# Boost-Shield-V1_5.net
KiCad netlist of a schematic drawn in Altium Designer
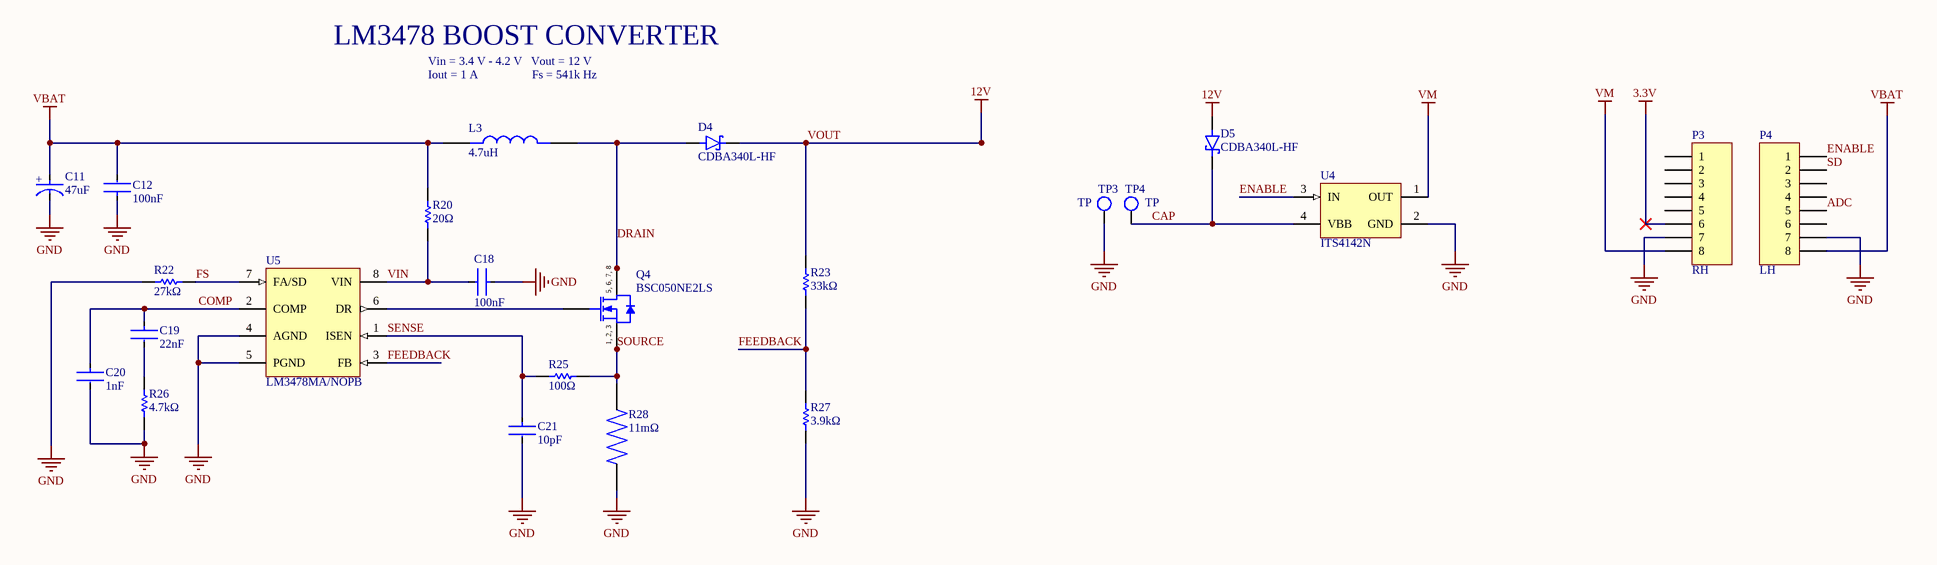
[diagram p0: Boost-Shield-V1.5.SchDoc]

(export (version "E")
  (design (tool "Eeschema 10.0.6"))
  (components
    (comp (ref "C11")
      (value "47uF")
      (footprint "FP-F38M-MFG")
      (description "CAP TANT POLY 47UF 6.3V SMD \r\nF380J476MMAAXEH3")
      (fields
        (field (name "OCTOPART") "https://octopart.com/f380j476mmaaxeh3-avx-67040374")
        (field (name "MANUFACTURER") "AVX")
      )
      (libsource (lib "Altium Content Vault") (part "cf48714ba7e38822c1575c7ec0b6d1f"))
    )
    (comp (ref "C12")
      (value "100nF")
      (footprint "FP-CL10-IPC_C")
      (description "Cap Ceramic 100nF 50V X7R ±20% Pad SMD 0603 +125°C T/R\r\nCL10B104MB8NNNC")
      (fields (field (name "TOLERANCE") "20%"))
      (libsource (lib "Altium Content Vault") (part "b4654b650e69147ec39a6b967a45e02"))
    )
    (comp (ref "C18")
      (value "100nF")
      (footprint "FP-CL10-IPC_C")
      (description "Cap Ceramic 100nF 50V X7R ±20% Pad SMD 0603 +125°C T/R\r\nCL10B104MB8NNNC")
      (fields (field (name "TOLERANCE") "20%"))
      (libsource (lib "Altium Content Vault") (part "b4654b650e69147ec39a6b967a45e02"))
    )
    (comp (ref "C19")
      (value "22nF")
      (footprint "FP-CC0603-DA-MFG")
      (description "0603 22 nF 50 V ±10 % Tolerance X7R SMT Multilayer Ceramic Capacitor\r\nCC0603KRX7R9BB223")
      (fields
        (field (name "MANUFACTURER") "YAGEO")
        (field (name "MANUFACTURER PART NUMBER") "CC0603KRX7R9BB223")
      )
      (libsource (lib "Altium Content Vault") (part "11868f565c42a9108669ba33697ecf6"))
    )
    (comp (ref "C20")
      (value "1nF")
      (footprint "FP-0603-L_1_6_0_15-W_0_81-IPC_C")
      (description "CAP CER 10000PF 50V X7R 0603\r\n06035C103KAT4A")
      (fields (field (name "TOLERANCE") "10%") (field (name "VOLTAGE") "50V"))
      (libsource (lib "Altium Content Vault") (part "02cd4be3c70576c341d710602a673aa"))
    )
    (comp (ref "C21")
      (value "10pF")
      (footprint "FP-C0603C-CF-MFG")
      (description "CAP CER 10PF 100V 5% NP0 0603\r\nC0603C100J1GACTU")
      (fields
        (field (name "MANUFACTURER PART NUMBER") "C0603C100J1GACTU")
        (field (name "MANUFACTURER") "KEMET")
      )
      (libsource (lib "Altium Content Vault") (part "b4654b650e69147ec39a6b967a45e02"))
    )
    (comp (ref "D4")
      (value "CDBA340L-HF")
      (footprint "DIOM5225X250N")
      (description "DIODE SCHOTTKY 40V 3A DO214AC")
      (fields (field (name "MANUFACTURER") "Comchip"))
      (libsource (lib "Boost-Shield") (part "CDBA340L-HF"))
    )
    (comp (ref "D5")
      (value "CDBA340L-HF")
      (footprint "DIOM5225X250N")
      (description "DIODE SCHOTTKY 40V 3A DO214AC")
      (fields (field (name "MANUFACTURER") "Comchip"))
      (libsource (lib "Boost-Shield") (part "CDBA340L-HF"))
    )
    (comp (ref "L3")
      (value "4.7uH")
      (footprint "IND_ETQP4M4R7KFN")
      (description "Fixed Ind 4.7UH 7.3A 22.77MOHM")
      (fields
        (field (name "MANUFACTURER") "Panasonic")
        (field (name "MANUFACTURER PART NUMBER") "ETQ-P4M4R7KFN")
      )
      (libsource (lib "Boost-Shield") (part "ETQ-P4M4R7KFN"))
    )
    (comp (ref "P3")
      (value "RH")
      (footprint "HDR1X8")
      (description "Header, 8-Pin")
      (fields (field (name "PUBLISHER") "Altium Limited"))
      (libsource (lib "") (part "Header 8_1"))
    )
    (comp (ref "P4")
      (value "LH")
      (footprint "HDR1X8")
      (description "Header, 8-Pin")
      (fields (field (name "PUBLISHER") "Altium Limited"))
      (libsource (lib "Miscellaneous Connectors") (part "Header 8"))
    )
    (comp (ref "Q4")
      (value "BSC050NE2LS")
      (footprint "INF-PG-TDSON-8-1_V")
      (description "N-Channel OptiMOS Power-MOSFET, 25 V VDS, 58 A ID, -55 to 150 degC, PG-TDSON-8-1, Reel, Green")
      (fields (field (name "MANUFACTURER") "Infineon"))
      (libsource (lib "Altium Content Vault") (part "INF-NEMOS-SSSGDDDD-8"))
    )
    (comp (ref "R20")
      (value "20Ω")
      (footprint "RESC1608X55X30ML15T15")
      (description "ERJ-3GEYJ200V")
      (fields (field (name "MANUFACTURER") "Panasonic"))
      (libsource (lib "Altium Content Vault") (part "RES"))
    )
    (comp (ref "R22")
      (value "27kΩ")
      (footprint "RESC1608X55X30ML15T15")
      (description "ERJ3EKF2702V")
      (fields (field (name "MANUFACTURER") "Panasonic"))
      (libsource (lib "Altium Content Vault") (part "RES"))
    )
    (comp (ref "R23")
      (value "33kΩ")
      (footprint "RESC1609X50X30LL10T20")
      (description "CRCW060333K0JNEA")
      (fields (field (name "MANUFACTURER") "Vishay Dale"))
      (libsource (lib "Altium Content Vault") (part "RES"))
    )
    (comp (ref "R25")
      (value "100Ω")
      (footprint "RESC1609X50X30ML8T20")
      (fields (field (name "MANUFACTURER") "Vishay Semiconductor"))
      (libsource (lib "Altium Content Vault") (part "RES-2"))
    )
    (comp (ref "R26")
      (value "4.7kΩ")
      (footprint "RESC1608X55X30NL15T15")
      (fields (field (name "TOLERANCE") "5%"))
      (libsource (lib "Altium Content Vault") (part "RES-2"))
    )
    (comp (ref "R27")
      (value "3.9kΩ")
      (footprint "RESC1608X55X30LL15T15")
      (description "ERJ-3GEYJ392V")
      (fields (field (name "MANUFACTURER") "Panasonic"))
      (libsource (lib "Altium Content Vault") (part "RES"))
    )
    (comp (ref "R28")
      (value "11mΩ")
      (footprint "RESC3115X65N")
      (description "11 mOhms ±1% 0.5W, 1/2W Chip Resistor 1206 (3216 Metric) Current Sense Thick Film")
      (libsource (lib "Boost-Shield") (part "RLP73V2BR011FTDF"))
    )
    (comp (ref "TP3") (value "TP") (footprint "TP") (libsource (lib "Boost-Shield") (part "TP")))
    (comp (ref "TP4") (value "TP") (footprint "TP") (libsource (lib "Boost-Shield") (part "TP")))
    (comp (ref "U4")
      (value "ITS4142N")
      (footprint "INF-SOT223_M")
      (fields (field (name "MANUFACTURER") "Infineon"))
      (libsource (lib "Altium Content Vault") (part "INF-ITS4142N-SOT223-4"))
    )
    (comp (ref "U5")
      (value "LM3478MA/NOPB")
      (footprint "D0008A_L")
      (fields (field (name "MANUFACTURER") "Texas Instruments"))
      (libsource (lib "Altium Content Vault") (part "PM-SWREG-LM3478-8"))
    )
  )
  (nets
    (net (code "1") (name "/ADC") (class "Default")
      (node (ref "P4") (pin "5") (pinfunction "5_5") (pintype "passive"))
    )
    (net (code "2") (name "/CAP") (class "Default")
      (node (ref "D5") (pin "C") (pinfunction "K_C") (pintype "passive"))
      (node (ref "TP4") (pin "1") (pinfunction "1_1") (pintype "passive"))
      (node (ref "U4") (pin "4") (pinfunction "VBB_4") (pintype "power_in"))
    )
    (net (code "3") (name "/COMP") (class "Default")
      (node (ref "C19") (pin "1") (pinfunction "1_1") (pintype "passive"))
      (node (ref "C20") (pin "1") (pinfunction "1_1") (pintype "passive"))
      (node (ref "U5") (pin "2") (pinfunction "COMP_2") (pintype "passive"))
    )
    (net (code "4") (name "/DRAIN") (class "Default")
      (node (ref "D4") (pin "A") (pinfunction "A_A") (pintype "passive"))
      (node (ref "L3") (pin "2") (pinfunction "2_2") (pintype "passive"))
      (node (ref "Q4") (pin "5") (pinfunction "DRAIN_5") (pintype "passive"))
      (node (ref "Q4") (pin "6") (pinfunction "DRAIN_6") (pintype "passive"))
      (node (ref "Q4") (pin "7") (pinfunction "DRAIN_7") (pintype "passive"))
      (node (ref "Q4") (pin "8") (pinfunction "DRAIN_8") (pintype "passive"))
    )
    (net (code "5") (name "/ENABLE") (class "Default")
      (node (ref "P4") (pin "1") (pinfunction "1_1") (pintype "passive"))
      (node (ref "U4") (pin "3") (pinfunction "IN_3") (pintype "input"))
    )
    (net (code "6") (name "/FEEDBACK") (class "Default")
      (node (ref "R23") (pin "1") (pinfunction "1_1") (pintype "passive"))
      (node (ref "R27") (pin "2") (pinfunction "2_2") (pintype "passive"))
      (node (ref "U5") (pin "3") (pinfunction "FB_3") (pintype "input"))
    )
    (net (code "7") (name "/FS") (class "Default")
      (node (ref "R22") (pin "2") (pinfunction "2_2") (pintype "passive"))
      (node (ref "U5") (pin "7") (pinfunction "FA/SD_7") (pintype "input"))
    )
    (net (code "8") (name "/SD") (class "Default")
      (node (ref "P4") (pin "2") (pinfunction "2_2") (pintype "passive"))
    )
    (net (code "9") (name "/SENSE") (class "Default")
      (node (ref "C21") (pin "1") (pinfunction "1_1") (pintype "passive"))
      (node (ref "R25") (pin "1") (pinfunction "1_1") (pintype "passive"))
      (node (ref "U5") (pin "1") (pinfunction "ISEN_1") (pintype "input"))
    )
    (net (code "10") (name "/SOURCE") (class "Default")
      (node (ref "Q4") (pin "1") (pinfunction "SOURCE_1") (pintype "passive"))
      (node (ref "Q4") (pin "2") (pinfunction "SOURCE_2") (pintype "passive"))
      (node (ref "Q4") (pin "3") (pinfunction "SOURCE_3") (pintype "passive"))
      (node (ref "R25") (pin "2") (pinfunction "2_2") (pintype "passive"))
      (node (ref "R28") (pin "2") (pinfunction "2_2") (pintype "passive"))
    )
    (net (code "11") (name "/VIN") (class "Default")
      (node (ref "C18") (pin "2") (pinfunction "2_2") (pintype "passive"))
      (node (ref "R20") (pin "1") (pinfunction "1_1") (pintype "passive"))
      (node (ref "U5") (pin "8") (pinfunction "VIN_8") (pintype "power_in"))
    )
    (net (code "12") (name "3.3V") (class "Default")
      (node (ref "P3") (pin "6") (pinfunction "6_6") (pintype "passive"))
    )
    (net (code "13") (name "12V") (class "Default")
      (node (ref "D4") (pin "C") (pinfunction "K_C") (pintype "passive"))
      (node (ref "D5") (pin "A") (pinfunction "A_A") (pintype "passive"))
      (node (ref "R23") (pin "2") (pinfunction "2_2") (pintype "passive"))
    )
    (net (code "14") (name "GND") (class "Default")
      (node (ref "C11") (pin "1") (pinfunction "C_1") (pintype "passive"))
      (node (ref "C12") (pin "1") (pinfunction "1_1") (pintype "passive"))
      (node (ref "C18") (pin "1") (pinfunction "1_1") (pintype "passive"))
      (node (ref "C20") (pin "2") (pinfunction "2_2") (pintype "passive"))
      (node (ref "C21") (pin "2") (pinfunction "2_2") (pintype "passive"))
      (node (ref "P3") (pin "7") (pinfunction "7_7") (pintype "passive"))
      (node (ref "P4") (pin "7") (pinfunction "7_7") (pintype "passive"))
      (node (ref "R22") (pin "1") (pinfunction "1_1") (pintype "passive"))
      (node (ref "R26") (pin "1") (pinfunction "1_1") (pintype "passive"))
      (node (ref "R27") (pin "1") (pinfunction "1_1") (pintype "passive"))
      (node (ref "R28") (pin "1") (pinfunction "1_1") (pintype "passive"))
      (node (ref "TP3") (pin "1") (pinfunction "1_1") (pintype "passive"))
      (node (ref "U4") (pin "2") (pinfunction "GND_2") (pintype "power_in"))
      (node (ref "U5") (pin "4") (pinfunction "AGND_4") (pintype "power_in"))
      (node (ref "U5") (pin "5") (pinfunction "PGND_5") (pintype "power_in"))
    )
    (net (code "15") (name "Net-(C19-Pad2)") (class "Default")
      (node (ref "C19") (pin "2") (pinfunction "2_2") (pintype "passive"))
      (node (ref "R26") (pin "2") (pinfunction "2_2") (pintype "passive"))
    )
    (net (code "16") (name "Net-(Q4-GATE)") (class "Default")
      (node (ref "Q4") (pin "4") (pinfunction "GATE_4") (pintype "passive"))
      (node (ref "U5") (pin "6") (pinfunction "DR_6") (pintype "output"))
    )
    (net (code "17") (name "VBAT") (class "Default")
      (node (ref "C11") (pin "2") (pinfunction "A_2") (pintype "passive"))
      (node (ref "C12") (pin "2") (pinfunction "2_2") (pintype "passive"))
      (node (ref "L3") (pin "1") (pinfunction "1_1") (pintype "passive"))
      (node (ref "P4") (pin "8") (pinfunction "8_8") (pintype "passive"))
      (node (ref "R20") (pin "2") (pinfunction "2_2") (pintype "passive"))
    )
    (net (code "18") (name "VM") (class "Default")
      (node (ref "P3") (pin "8") (pinfunction "8_8") (pintype "passive"))
      (node (ref "U4") (pin "1") (pinfunction "OUT_1") (pintype "power_in"))
    )
    (net (code "19") (name "unconnected-(P3-Pad1)") (class "Default")
      (node (ref "P3") (pin "1") (pinfunction "1_1") (pintype "passive"))
    )
    (net (code "20") (name "unconnected-(P3-Pad2)") (class "Default")
      (node (ref "P3") (pin "2") (pinfunction "2_2") (pintype "passive"))
    )
    (net (code "21") (name "unconnected-(P3-Pad3)") (class "Default")
      (node (ref "P3") (pin "3") (pinfunction "3_3") (pintype "passive"))
    )
    (net (code "22") (name "unconnected-(P3-Pad4)") (class "Default")
      (node (ref "P3") (pin "4") (pinfunction "4_4") (pintype "passive"))
    )
    (net (code "23") (name "unconnected-(P3-Pad5)") (class "Default")
      (node (ref "P3") (pin "5") (pinfunction "5_5") (pintype "passive"))
    )
    (net (code "24") (name "unconnected-(P4-Pad3)") (class "Default")
      (node (ref "P4") (pin "3") (pinfunction "3_3") (pintype "passive"))
    )
    (net (code "25") (name "unconnected-(P4-Pad4)") (class "Default")
      (node (ref "P4") (pin "4") (pinfunction "4_4") (pintype "passive"))
    )
    (net (code "26") (name "unconnected-(P4-Pad6)") (class "Default")
      (node (ref "P4") (pin "6") (pinfunction "6_6") (pintype "passive"))
    )
  )
)
